# eNode3.net
KiCad netlist of a schematic drawn in EAGLE
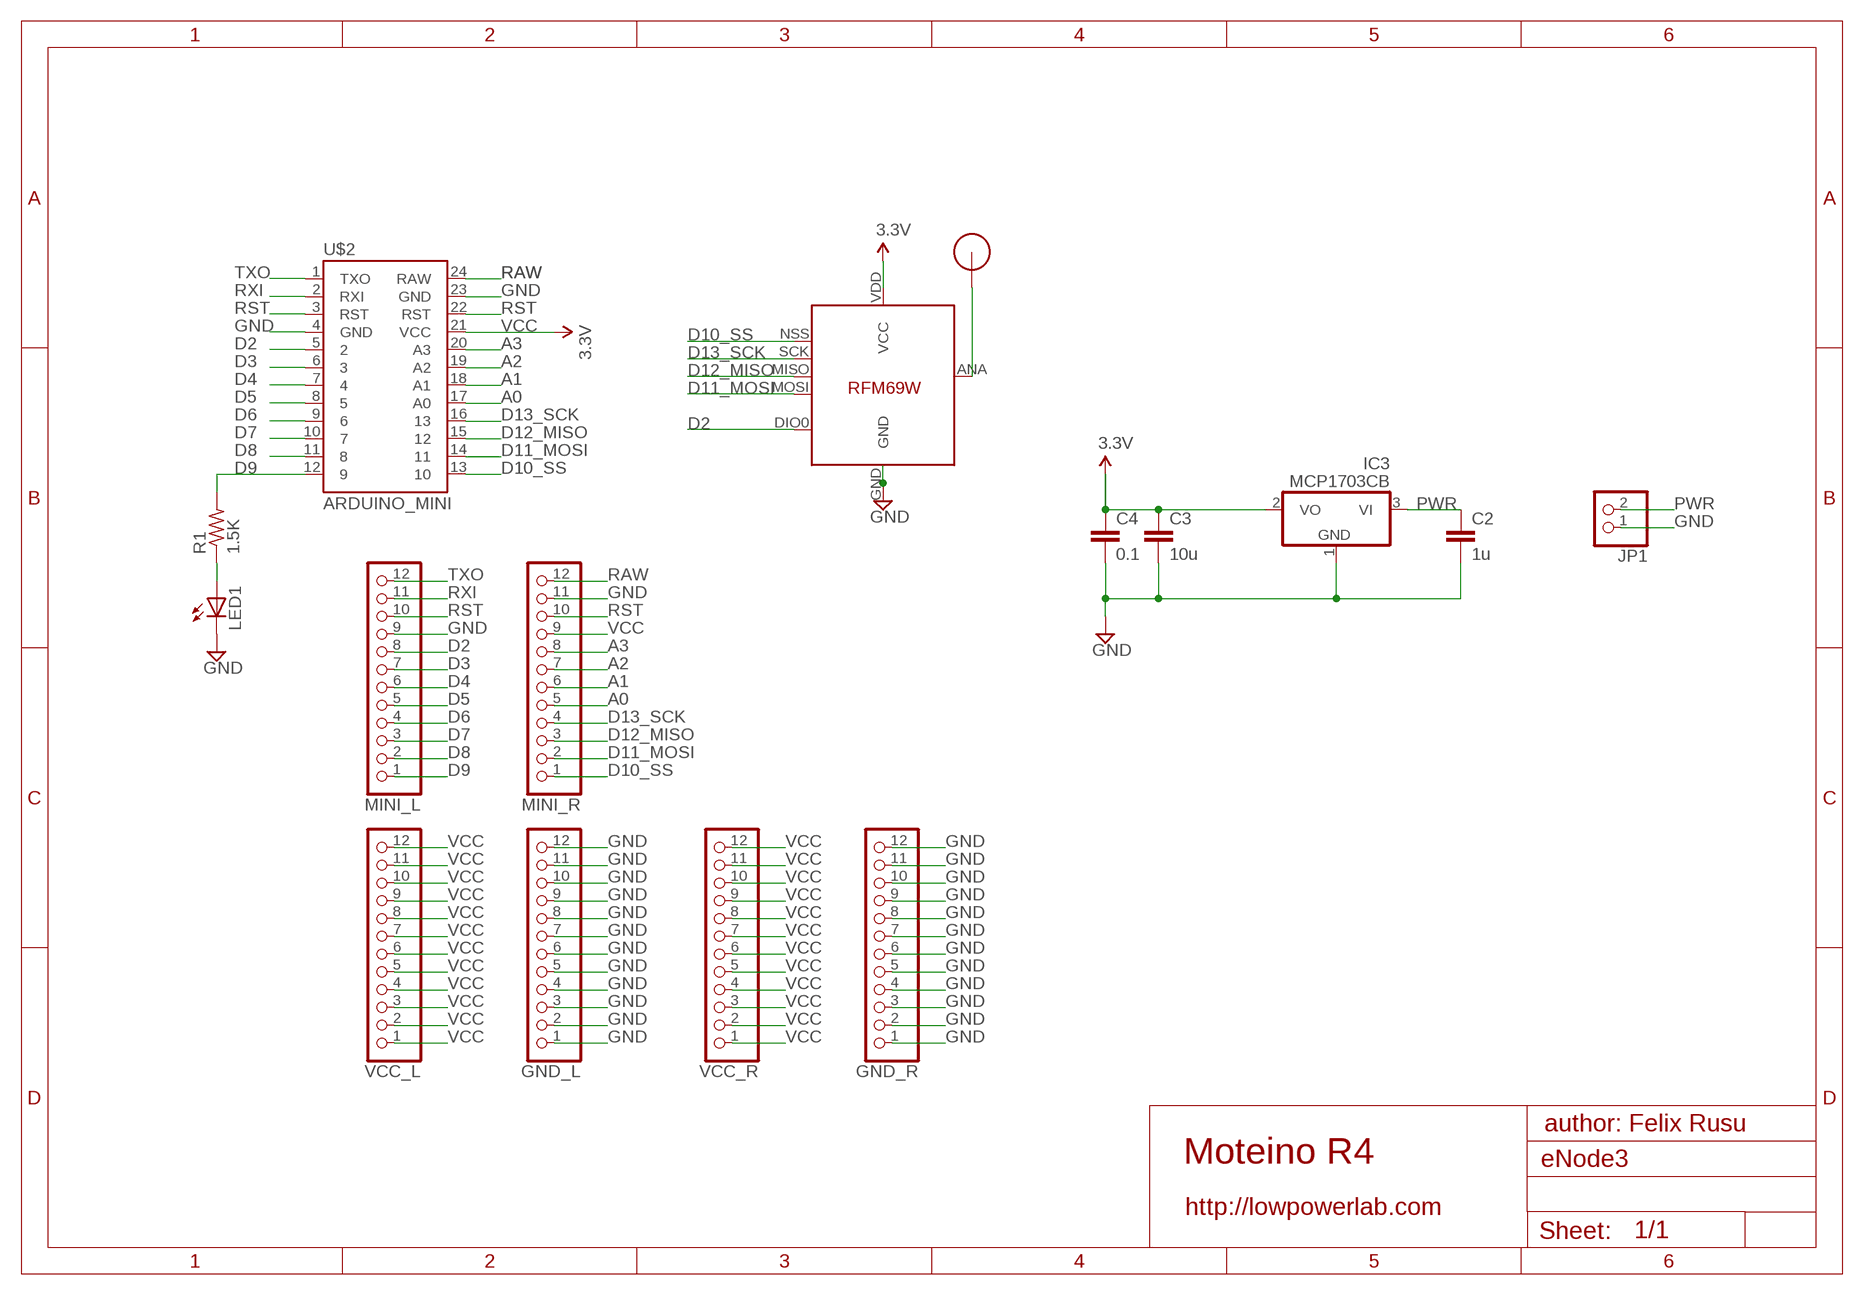
[diagram p0: schematic, sheet 1]

(export (version "E")
  (design (tool "Eeschema 10.0.6"))
  (components
    (comp (ref "C2")
      (value "1u")
      (footprint "eagle-import:0603-CAP")
      (libsource (lib "eagle-import") (part "CAP0603-CAP"))
    )
    (comp (ref "C3")
      (value "10u")
      (footprint "eagle-import:0805-CAP")
      (libsource (lib "eagle-import") (part "CAP0805-CAP"))
    )
    (comp (ref "C4")
      (value "0.1")
      (footprint "eagle-import:0603-CAP")
      (libsource (lib "eagle-import") (part "CAP0603-CAP"))
    )
    (comp (ref "GND_L")
      (value "PINHD-1X12-CB")
      (footprint "eagle-import:1X12-CB")
      (libsource (lib "eagle-import") (part "PINHD-1X12-CB"))
    )
    (comp (ref "GND_R")
      (value "PINHD-1X12-CB")
      (footprint "eagle-import:1X12-CB")
      (libsource (lib "eagle-import") (part "PINHD-1X12-CB"))
    )
    (comp (ref "IC3")
      (value "MCP1703CB")
      (footprint "eagle-import:SOT23")
      (libsource (lib "eagle-import") (part "MCP1703CB"))
    )
    (comp (ref "JP1")
      (value "PINHD-1X2")
      (footprint "eagle-import:1X02")
      (libsource (lib "eagle-import") (part "PINHD-1X2"))
    )
    (comp (ref "LED1")
      (value "LED3MM")
      (footprint "eagle-import:LED3MM")
      (libsource (lib "eagle-import") (part "LED3MM"))
    )
    (comp (ref "MINI_L")
      (value "PINHD-1X12-CB")
      (footprint "eagle-import:1X12-CB")
      (libsource (lib "eagle-import") (part "PINHD-1X12-CB"))
    )
    (comp (ref "MINI_R")
      (value "PINHD-1X12-CB")
      (footprint "eagle-import:1X12-CB")
      (libsource (lib "eagle-import") (part "PINHD-1X12-CB"))
    )
    (comp (ref "R1")
      (value "1.5K")
      (footprint "eagle-import:R0805")
      (libsource (lib "eagle-import") (part "R-US_R0805"))
    )
    (comp (ref "U$1")
      (value "RFM12B_ANTENNA")
      (footprint "eagle-import:RFM12B-ANTENNA")
      (libsource (lib "eagle-import") (part "RFM12B_ANTENNA"))
    )
    (comp (ref "U$2")
      (value "ARDUINO_MINI")
      (footprint "eagle-import:ARDUINO_MINI")
      (libsource (lib "eagle-import") (part "ARDUINO_MINI"))
    )
    (comp (ref "U$5")
      (value "RFM69")
      (footprint "eagle-import:RFM69W-MINPADS")
      (libsource (lib "eagle-import") (part "RFM69"))
    )
    (comp (ref "VCC_L")
      (value "PINHD-1X12-CB")
      (footprint "eagle-import:1X12-CB")
      (libsource (lib "eagle-import") (part "PINHD-1X12-CB"))
    )
    (comp (ref "VCC_R")
      (value "PINHD-1X12-CB")
      (footprint "eagle-import:1X12-CB")
      (libsource (lib "eagle-import") (part "PINHD-1X12-CB"))
    )
  )
  (nets
    (net (code "1") (name "/A0") (class "Default")
      (node (ref "MINI_R") (pin "5") (pinfunction "5_5") (pintype "passive"))
      (node (ref "U$2") (pin "17") (pinfunction "A0_17") (pintype "bidirectional"))
    )
    (net (code "2") (name "/A1") (class "Default")
      (node (ref "MINI_R") (pin "6") (pinfunction "6_6") (pintype "passive"))
      (node (ref "U$2") (pin "18") (pinfunction "A1_18") (pintype "bidirectional"))
    )
    (net (code "3") (name "/A2") (class "Default")
      (node (ref "MINI_R") (pin "7") (pinfunction "7_7") (pintype "passive"))
      (node (ref "U$2") (pin "19") (pinfunction "A2_19") (pintype "bidirectional"))
    )
    (net (code "4") (name "/A3") (class "Default")
      (node (ref "MINI_R") (pin "8") (pinfunction "8_8") (pintype "passive"))
      (node (ref "U$2") (pin "20") (pinfunction "A3_20") (pintype "bidirectional"))
    )
    (net (code "5") (name "/D2") (class "Default")
      (node (ref "MINI_L") (pin "8") (pinfunction "8_8") (pintype "passive"))
      (node (ref "U$2") (pin "5") (pinfunction "2_5") (pintype "bidirectional"))
      (node (ref "U$5") (pin "DIO0") (pinfunction "DIO0_DIO0") (pintype "open_collector"))
    )
    (net (code "6") (name "/D3") (class "Default")
      (node (ref "MINI_L") (pin "7") (pinfunction "7_7") (pintype "passive"))
      (node (ref "U$2") (pin "6") (pinfunction "3_6") (pintype "bidirectional"))
    )
    (net (code "7") (name "/D4") (class "Default")
      (node (ref "MINI_L") (pin "6") (pinfunction "6_6") (pintype "passive"))
      (node (ref "U$2") (pin "7") (pinfunction "4_7") (pintype "bidirectional"))
    )
    (net (code "8") (name "/D5") (class "Default")
      (node (ref "MINI_L") (pin "5") (pinfunction "5_5") (pintype "passive"))
      (node (ref "U$2") (pin "8") (pinfunction "5_8") (pintype "bidirectional"))
    )
    (net (code "9") (name "/D6") (class "Default")
      (node (ref "MINI_L") (pin "4") (pinfunction "4_4") (pintype "passive"))
      (node (ref "U$2") (pin "9") (pinfunction "6_9") (pintype "bidirectional"))
    )
    (net (code "10") (name "/D7") (class "Default")
      (node (ref "MINI_L") (pin "3") (pinfunction "3_3") (pintype "passive"))
      (node (ref "U$2") (pin "10") (pinfunction "7_10") (pintype "bidirectional"))
    )
    (net (code "11") (name "/D8") (class "Default")
      (node (ref "MINI_L") (pin "2") (pinfunction "2_2") (pintype "passive"))
      (node (ref "U$2") (pin "11") (pinfunction "8_11") (pintype "bidirectional"))
    )
    (net (code "12") (name "/D9") (class "Default")
      (node (ref "MINI_L") (pin "1") (pinfunction "1_1") (pintype "passive"))
      (node (ref "R1") (pin "2") (pinfunction "2_2") (pintype "passive"))
      (node (ref "U$2") (pin "12") (pinfunction "9_12") (pintype "bidirectional"))
    )
    (net (code "13") (name "/D10_SS") (class "Default")
      (node (ref "MINI_R") (pin "1") (pinfunction "1_1") (pintype "passive"))
      (node (ref "U$2") (pin "13") (pinfunction "10_13") (pintype "bidirectional"))
      (node (ref "U$5") (pin "NSS") (pinfunction "SEL_NSS") (pintype "input"))
    )
    (net (code "14") (name "/D11_MOSI") (class "Default")
      (node (ref "MINI_R") (pin "2") (pinfunction "2_2") (pintype "passive"))
      (node (ref "U$2") (pin "14") (pinfunction "11_14") (pintype "bidirectional"))
      (node (ref "U$5") (pin "MOSI") (pinfunction "MOSI_MOSI") (pintype "output"))
    )
    (net (code "15") (name "/D12_MISO") (class "Default")
      (node (ref "MINI_R") (pin "3") (pinfunction "3_3") (pintype "passive"))
      (node (ref "U$2") (pin "15") (pinfunction "12_15") (pintype "bidirectional"))
      (node (ref "U$5") (pin "MISO") (pinfunction "MISO_MISO") (pintype "input"))
    )
    (net (code "16") (name "/D13_SCK") (class "Default")
      (node (ref "MINI_R") (pin "4") (pinfunction "4_4") (pintype "passive"))
      (node (ref "U$2") (pin "16") (pinfunction "13_16") (pintype "bidirectional"))
      (node (ref "U$5") (pin "SCK") (pinfunction "SCK_SCK") (pintype "input"))
    )
    (net (code "17") (name "/PWR") (class "Default")
      (node (ref "C2") (pin "1") (pinfunction "1_1") (pintype "passive"))
      (node (ref "IC3") (pin "3") (pinfunction "VI_3") (pintype "input"))
      (node (ref "JP1") (pin "2") (pinfunction "2_2") (pintype "passive"))
    )
    (net (code "18") (name "/RAW") (class "Default")
      (node (ref "MINI_R") (pin "12") (pinfunction "12_12") (pintype "passive"))
      (node (ref "U$2") (pin "24") (pinfunction "RAW_24") (pintype "bidirectional"))
    )
    (net (code "19") (name "/RST") (class "Default")
      (node (ref "MINI_L") (pin "10") (pinfunction "10_10") (pintype "passive"))
      (node (ref "MINI_R") (pin "10") (pinfunction "10_10") (pintype "passive"))
      (node (ref "U$2") (pin "22") (pinfunction "RST_22") (pintype "bidirectional"))
      (node (ref "U$2") (pin "3") (pinfunction "RST_3") (pintype "bidirectional"))
    )
    (net (code "20") (name "/RXI") (class "Default")
      (node (ref "MINI_L") (pin "11") (pinfunction "11_11") (pintype "passive"))
      (node (ref "U$2") (pin "2") (pinfunction "RXI_2") (pintype "bidirectional"))
    )
    (net (code "21") (name "/TXO") (class "Default")
      (node (ref "MINI_L") (pin "12") (pinfunction "12_12") (pintype "passive"))
      (node (ref "U$2") (pin "1") (pinfunction "TXO_1") (pintype "bidirectional"))
    )
    (net (code "22") (name "3.3V") (class "Default")
      (node (ref "C3") (pin "1") (pinfunction "1_1") (pintype "passive"))
      (node (ref "C4") (pin "1") (pinfunction "1_1") (pintype "passive"))
      (node (ref "IC3") (pin "2") (pinfunction "VO_2") (pintype "passive"))
      (node (ref "MINI_R") (pin "9") (pinfunction "9_9") (pintype "passive"))
      (node (ref "U$2") (pin "21") (pinfunction "VCC_21") (pintype "bidirectional"))
      (node (ref "U$5") (pin "VDD") (pinfunction "VCC_VDD") (pintype "power_in"))
      (node (ref "VCC_L") (pin "1") (pinfunction "1_1") (pintype "passive"))
      (node (ref "VCC_L") (pin "10") (pinfunction "10_10") (pintype "passive"))
      (node (ref "VCC_L") (pin "11") (pinfunction "11_11") (pintype "passive"))
      (node (ref "VCC_L") (pin "12") (pinfunction "12_12") (pintype "passive"))
      (node (ref "VCC_L") (pin "2") (pinfunction "2_2") (pintype "passive"))
      (node (ref "VCC_L") (pin "3") (pinfunction "3_3") (pintype "passive"))
      (node (ref "VCC_L") (pin "4") (pinfunction "4_4") (pintype "passive"))
      (node (ref "VCC_L") (pin "5") (pinfunction "5_5") (pintype "passive"))
      (node (ref "VCC_L") (pin "6") (pinfunction "6_6") (pintype "passive"))
      (node (ref "VCC_L") (pin "7") (pinfunction "7_7") (pintype "passive"))
      (node (ref "VCC_L") (pin "8") (pinfunction "8_8") (pintype "passive"))
      (node (ref "VCC_L") (pin "9") (pinfunction "9_9") (pintype "passive"))
      (node (ref "VCC_R") (pin "1") (pinfunction "1_1") (pintype "passive"))
      (node (ref "VCC_R") (pin "10") (pinfunction "10_10") (pintype "passive"))
      (node (ref "VCC_R") (pin "11") (pinfunction "11_11") (pintype "passive"))
      (node (ref "VCC_R") (pin "12") (pinfunction "12_12") (pintype "passive"))
      (node (ref "VCC_R") (pin "2") (pinfunction "2_2") (pintype "passive"))
      (node (ref "VCC_R") (pin "3") (pinfunction "3_3") (pintype "passive"))
      (node (ref "VCC_R") (pin "4") (pinfunction "4_4") (pintype "passive"))
      (node (ref "VCC_R") (pin "5") (pinfunction "5_5") (pintype "passive"))
      (node (ref "VCC_R") (pin "6") (pinfunction "6_6") (pintype "passive"))
      (node (ref "VCC_R") (pin "7") (pinfunction "7_7") (pintype "passive"))
      (node (ref "VCC_R") (pin "8") (pinfunction "8_8") (pintype "passive"))
      (node (ref "VCC_R") (pin "9") (pinfunction "9_9") (pintype "passive"))
    )
    (net (code "23") (name "GND") (class "Default")
      (node (ref "C2") (pin "2") (pinfunction "2_2") (pintype "passive"))
      (node (ref "C3") (pin "2") (pinfunction "2_2") (pintype "passive"))
      (node (ref "C4") (pin "2") (pinfunction "2_2") (pintype "passive"))
      (node (ref "GND_L") (pin "1") (pinfunction "1_1") (pintype "passive"))
      (node (ref "GND_L") (pin "10") (pinfunction "10_10") (pintype "passive"))
      (node (ref "GND_L") (pin "11") (pinfunction "11_11") (pintype "passive"))
      (node (ref "GND_L") (pin "12") (pinfunction "12_12") (pintype "passive"))
      (node (ref "GND_L") (pin "2") (pinfunction "2_2") (pintype "passive"))
      (node (ref "GND_L") (pin "3") (pinfunction "3_3") (pintype "passive"))
      (node (ref "GND_L") (pin "4") (pinfunction "4_4") (pintype "passive"))
      (node (ref "GND_L") (pin "5") (pinfunction "5_5") (pintype "passive"))
      (node (ref "GND_L") (pin "6") (pinfunction "6_6") (pintype "passive"))
      (node (ref "GND_L") (pin "7") (pinfunction "7_7") (pintype "passive"))
      (node (ref "GND_L") (pin "8") (pinfunction "8_8") (pintype "passive"))
      (node (ref "GND_L") (pin "9") (pinfunction "9_9") (pintype "passive"))
      (node (ref "GND_R") (pin "1") (pinfunction "1_1") (pintype "passive"))
      (node (ref "GND_R") (pin "10") (pinfunction "10_10") (pintype "passive"))
      (node (ref "GND_R") (pin "11") (pinfunction "11_11") (pintype "passive"))
      (node (ref "GND_R") (pin "12") (pinfunction "12_12") (pintype "passive"))
      (node (ref "GND_R") (pin "2") (pinfunction "2_2") (pintype "passive"))
      (node (ref "GND_R") (pin "3") (pinfunction "3_3") (pintype "passive"))
      (node (ref "GND_R") (pin "4") (pinfunction "4_4") (pintype "passive"))
      (node (ref "GND_R") (pin "5") (pinfunction "5_5") (pintype "passive"))
      (node (ref "GND_R") (pin "6") (pinfunction "6_6") (pintype "passive"))
      (node (ref "GND_R") (pin "7") (pinfunction "7_7") (pintype "passive"))
      (node (ref "GND_R") (pin "8") (pinfunction "8_8") (pintype "passive"))
      (node (ref "GND_R") (pin "9") (pinfunction "9_9") (pintype "passive"))
      (node (ref "IC3") (pin "1") (pinfunction "GND_1") (pintype "passive"))
      (node (ref "JP1") (pin "1") (pinfunction "1_1") (pintype "passive"))
      (node (ref "LED1") (pin "K") (pinfunction "C_K") (pintype "passive"))
      (node (ref "MINI_L") (pin "9") (pinfunction "9_9") (pintype "passive"))
      (node (ref "MINI_R") (pin "11") (pinfunction "11_11") (pintype "passive"))
      (node (ref "U$2") (pin "23") (pinfunction "GND_23") (pintype "bidirectional"))
      (node (ref "U$2") (pin "4") (pinfunction "GND_4") (pintype "bidirectional"))
      (node (ref "U$5") (pin "GND") (pinfunction "GND_GND") (pintype "power_in"))
    )
    (net (code "24") (name "Net-(LED1-PadA)") (class "Default")
      (node (ref "LED1") (pin "A") (pinfunction "A_A") (pintype "passive"))
      (node (ref "R1") (pin "1") (pinfunction "1_1") (pintype "passive"))
    )
    (net (code "25") (name "Net-(U$1-1)") (class "Default")
      (node (ref "U$1") (pin "P$1") (pinfunction "1_P$1") (pintype "bidirectional"))
      (node (ref "U$5") (pin "ANA") (pinfunction "ANT_ANA") (pintype "passive"))
    )
  )
)
